# Microcontroller.net
KiCad netlist of a schematic drawn in Altium Designer
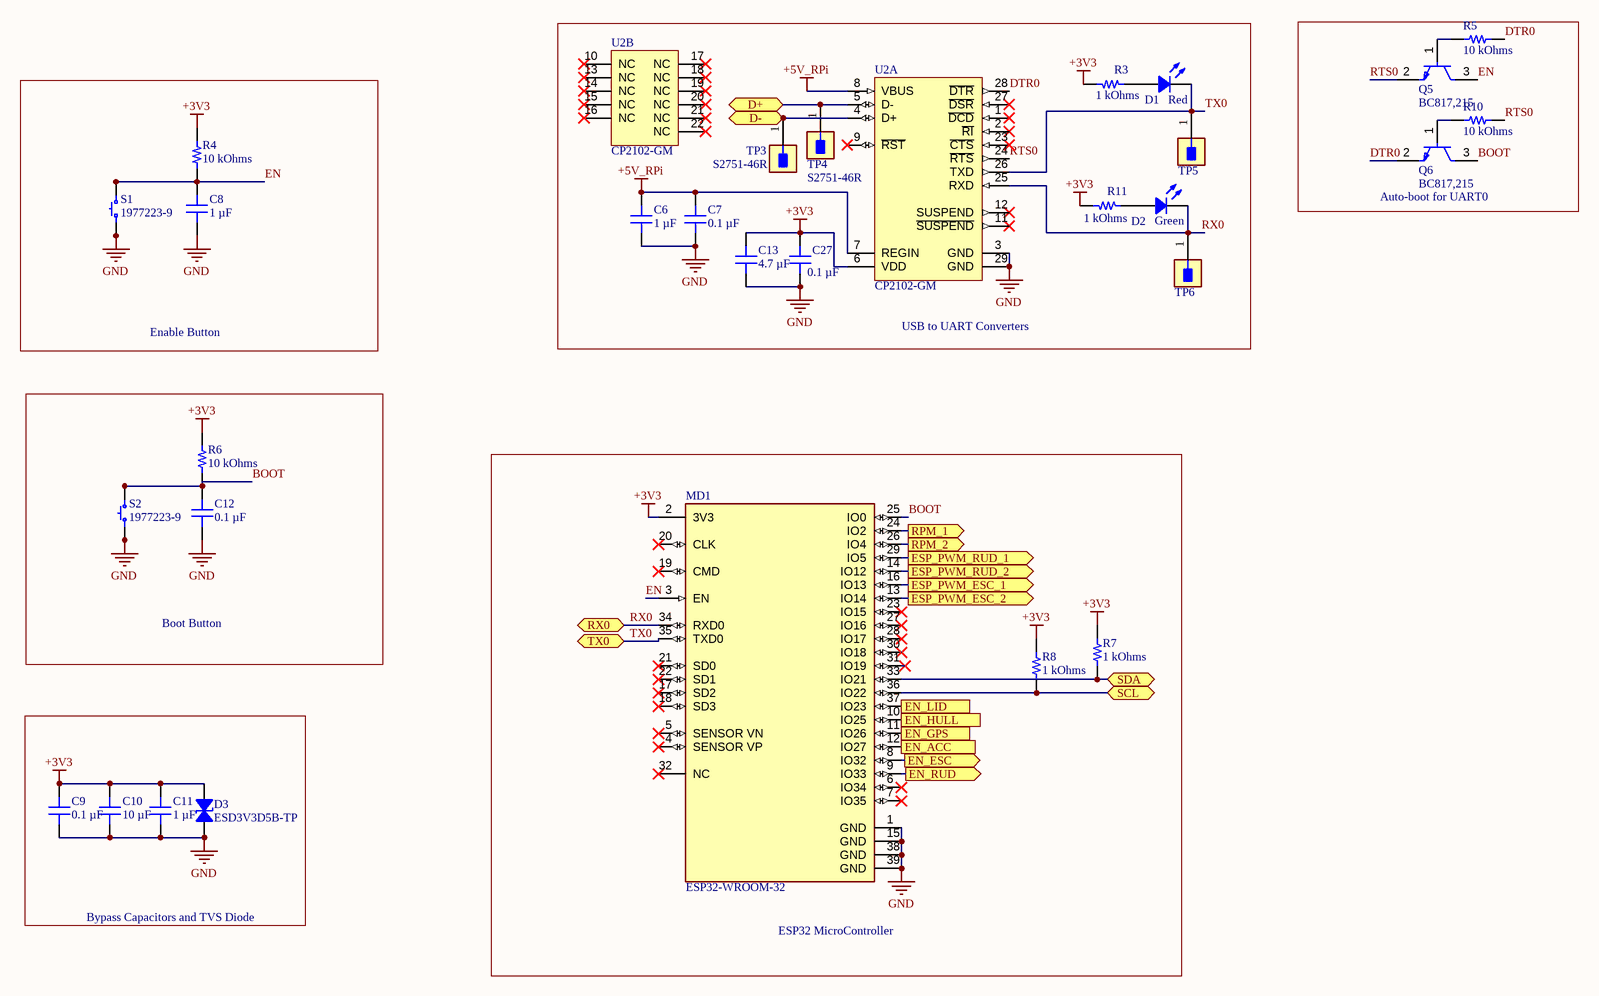
[diagram p0: Microcontroller.SchDoc]

(export (version "E")
  (design (tool "Eeschema 10.0.6"))
  (components
    (comp (ref "C6")
      (value "1 µF")
      (footprint "CAP 0603_1608")
      (description "CAP CER 1UF 35V X6S 0603")
      (fields
        (field (name "PART NUMBER") "GRT188C8YA105KE13D")
        (field (name "MANUFACTURER") "Murata Electronics")
      )
      (libsource (lib "Celestial Altium Library - altium_library") (part "Capacitor"))
    )
    (comp (ref "C7")
      (value "0.1 µF")
      (footprint "CAP 0603_1608")
      (description "CAP CER 0.1UF 25V X7R 0603")
      (fields (field (name "PART NUMBER") "C0603X104M3RAC7867") (field (name "MANUFACTURER") "KEMET"))
      (libsource (lib "Celestial Altium Library - altium_library") (part "Capacitor"))
    )
    (comp (ref "C8")
      (value "1 µF")
      (footprint "CAP 0603_1608")
      (description "CAP CER 1UF 16V X7R 0603")
      (fields (field (name "PART NUMBER") "CM105X7R105K16ATH") (field (name "MANUFACTURER") "KYOCERA AVX"))
      (libsource (lib "Celestial Altium Library - altium_library") (part "Capacitor"))
    )
    (comp (ref "C9")
      (value "0.1 µF")
      (footprint "CAP 0603_1608")
      (description "CAP CER 0.1UF 25V X7R 0603")
      (fields (field (name "PART NUMBER") "C0603X104M3RAC7867") (field (name "MANUFACTURER") "KEMET"))
      (libsource (lib "Celestial Altium Library - altium_library") (part "Capacitor"))
    )
    (comp (ref "C10")
      (value "10 µF")
      (footprint "CAP 0603_1608")
      (description "CAP CER 10UF 16V X5R 0603")
      (fields
        (field (name "PART NUMBER") "GRT188R61C106ME13D")
        (field (name "MANUFACTURER") "Murata Electronics")
      )
      (libsource (lib "Celestial Altium Library - altium_library") (part "Capacitor"))
    )
    (comp (ref "C11")
      (value "1 µF")
      (footprint "CAP 0603_1608")
      (description "CAP CER 1UF 16V X7R 0603")
      (fields (field (name "PART NUMBER") "CM105X7R105K16ATH") (field (name "MANUFACTURER") "KYOCERA AVX"))
      (libsource (lib "Celestial Altium Library - altium_library") (part "Capacitor"))
    )
    (comp (ref "C12")
      (value "0.1 µF")
      (footprint "CAP 0603_1608")
      (description "CAP CER 0.1UF 25V X7R 0603")
      (fields (field (name "PART NUMBER") "C0603X104M3RAC7867") (field (name "MANUFACTURER") "KEMET"))
      (libsource (lib "Celestial Altium Library - altium_library") (part "Capacitor"))
    )
    (comp (ref "C13")
      (value "4.7 µF")
      (footprint "CAP 0603_1608")
      (description "CAP CER 4.7UF 25V X6S 0603")
      (fields
        (field (name "PART NUMBER") "GRT188C81E475KE13D")
        (field (name "MANUFACTURER") "Murata Electronics")
      )
      (libsource (lib "Celestial Altium Library - altium_library") (part "Capacitor"))
    )
    (comp (ref "C27")
      (value "0.1 µF")
      (footprint "CAP 0603_1608")
      (description "CAP CER 0.1UF 25V X7R 0603")
      (fields (field (name "PART NUMBER") "C0603X104M3RAC7867") (field (name "MANUFACTURER") "KEMET"))
      (libsource (lib "Celestial Altium Library - altium_library") (part "Capacitor"))
    )
    (comp (ref "D1")
      (value "Red")
      (footprint "LED 0805_2012 RED")
      (description "LED RED CLEAR CHIP SMD")
      (fields (field (name "PART NUMBER") "XZUR54W-1") (field (name "MANUFACTURER") "SunLED"))
      (libsource (lib "Celestial Altium Library - altium_library") (part "LED"))
    )
    (comp (ref "D2")
      (value "Green")
      (footprint "LED 0805_2012 GREEN")
      (description "LED GREEN CLEAR CHIP SMD")
      (fields (field (name "PART NUMBER") "XZVG54W-1") (field (name "MANUFACTURER") "SunLED"))
      (libsource (lib "Celestial Altium Library - altium_library") (part "LED"))
    )
    (comp (ref "D3")
      (value "ESD3V3D5B-TP")
      (footprint "SOD523F")
      (description "TVS DIODE 3.3VWM 12VC SOD523")
      (fields (field (name "MANUFACTURER") "Micro Commercial Co"))
      (libsource (lib "Celestial Altium Library - altium_library") (part "Diode TVS"))
    )
    (comp (ref "MD1")
      (value "ESP32-WROOM-32")
      (footprint "FP-ESP32-WROOM-32-MFG")
      (description "RX TXRX MOD WIFI SURFACE MOUNT")
      (libsource (lib "Altium Content Vault") (part "ee866abf0b6c51247b7f5cdebf2f250"))
    )
    (comp (ref "Q5")
      (value "BC817,215")
      (footprint "FP-SOT23-IPC_C")
      (description "TRANS NPN 45V 500MA TO236AB")
      (libsource (lib "Altium Content Vault") (part "b44e953556f554d0102664c7d152cb4"))
    )
    (comp (ref "Q6")
      (value "BC817,215")
      (footprint "FP-SOT23-IPC_C")
      (description "TRANS NPN 45V 500MA TO236AB")
      (libsource (lib "Altium Content Vault") (part "b44e953556f554d0102664c7d152cb4"))
    )
    (comp (ref "R3")
      (value "1 kOhms")
      (footprint "RES 0603_1608")
      (description "RES SMD 1K OHM 1% 1/10W 0603")
      (fields (field (name "PART NUMBER") "CRCW06031K00FKEB") (field (name "MANUFACTURER") "Vishay Dale"))
      (libsource (lib "Celestial Altium Library - altium_library") (part "Resistor"))
    )
    (comp (ref "R4")
      (value "10 kOhms")
      (footprint "RES 0603_1608")
      (description "RES SMD 10K OHM 1% 1/10W 0603")
      (fields (field (name "PART NUMBER") "RT0603FRE0710KL") (field (name "MANUFACTURER") "Yageo"))
      (libsource (lib "Celestial Altium Library - altium_library") (part "Resistor"))
    )
    (comp (ref "R5")
      (value "10 kOhms")
      (footprint "RES 0603_1608")
      (description "RES 10K OHM 1% 1/5W 0603")
      (fields (field (name "PART NUMBER") "RC0603FR-7W10KL") (field (name "MANUFACTURER") "Yageo"))
      (libsource (lib "Celestial Altium Library - altium_library") (part "Resistor"))
    )
    (comp (ref "R6")
      (value "10 kOhms")
      (footprint "RES 0603_1608")
      (description "RES SMD 10K OHM 1% 1/10W 0603")
      (fields (field (name "PART NUMBER") "RT0603FRE0710KL") (field (name "MANUFACTURER") "Yageo"))
      (libsource (lib "Celestial Altium Library - altium_library") (part "Resistor"))
    )
    (comp (ref "R7")
      (value "1 kOhms")
      (footprint "RES 0603_1608")
      (description "RES SMD 1K OHM 1% 1/10W 0603")
      (fields (field (name "PART NUMBER") "CRCW06031K00FKEB") (field (name "MANUFACTURER") "Vishay Dale"))
      (libsource (lib "Celestial Altium Library - altium_library") (part "Resistor"))
    )
    (comp (ref "R8")
      (value "1 kOhms")
      (footprint "RES 0603_1608")
      (description "RES SMD 1K OHM 1% 1/10W 0603")
      (fields (field (name "PART NUMBER") "CRCW06031K00FKEB") (field (name "MANUFACTURER") "Vishay Dale"))
      (libsource (lib "Celestial Altium Library - altium_library") (part "Resistor"))
    )
    (comp (ref "R10")
      (value "10 kOhms")
      (footprint "RES 0603_1608")
      (description "RES 10K OHM 1% 1/5W 0603")
      (fields (field (name "PART NUMBER") "RC0603FR-7W10KL") (field (name "MANUFACTURER") "Yageo"))
      (libsource (lib "Celestial Altium Library - altium_library") (part "Resistor"))
    )
    (comp (ref "R11")
      (value "1 kOhms")
      (footprint "RES 0603_1608")
      (description "RES SMD 1K OHM 1% 1/10W 0603")
      (fields (field (name "PART NUMBER") "CRCW06031K00FKEB") (field (name "MANUFACTURER") "Vishay Dale"))
      (libsource (lib "Celestial Altium Library - altium_library") (part "Resistor"))
    )
    (comp (ref "S1")
      (value "1977223-9")
      (footprint "TE FSM4JSMA")
      (description "SWITCH TACTILE SPST-NO 0.05A 24V")
      (fields (field (name "MANUFACTURER") "TE Connectivity ALCOSWITCH Switches"))
      (libsource (lib "Celestial Altium Library - altium_library") (part "SPST-NO 4 PIN"))
    )
    (comp (ref "S2")
      (value "1977223-9")
      (footprint "TE FSM4JSMA")
      (description "SWITCH TACTILE SPST-NO 0.05A 24V")
      (fields (field (name "MANUFACTURER") "TE Connectivity ALCOSWITCH Switches"))
      (libsource (lib "Celestial Altium Library - altium_library") (part "SPST-NO 4 PIN"))
    )
    (comp (ref "TP3")
      (value "S2751-46R")
      (footprint "FP-S2751-46R-MFG")
      (description "Conn Test Point 1 POS Solder ST SMD 1 Port T/R")
      (libsource (lib "Americas- Environmental Engineering Club- University of Victoria") (part "dd45045ce8184df9e99e12baf3f412c"))
    )
    (comp (ref "TP4")
      (value "S2751-46R")
      (footprint "FP-S2751-46R-MFG")
      (description "Conn Test Point 1 POS Solder ST SMD 1 Port T/R")
      (libsource (lib "Americas- Environmental Engineering Club- University of Victoria") (part "dd45045ce8184df9e99e12baf3f412c"))
    )
    (comp (ref "TP5")
      (value "S2751-46R")
      (footprint "FP-S2751-46R-MFG")
      (description "Conn Test Point 1 POS Solder ST SMD 1 Port T/R")
      (libsource (lib "Americas- Environmental Engineering Club- University of Victoria") (part "dd45045ce8184df9e99e12baf3f412c"))
    )
    (comp (ref "TP6")
      (value "S2751-46R")
      (footprint "FP-S2751-46R-MFG")
      (description "Conn Test Point 1 POS Solder ST SMD 1 Port T/R")
      (libsource (lib "Americas- Environmental Engineering Club- University of Victoria") (part "dd45045ce8184df9e99e12baf3f412c"))
    )
    (comp (ref "U2")
      (value "CP2102-GM")
      (footprint "SLAB-QFN-28-3125x3125TP_N")
      (description "Single-Chip USB to UART Bridge, 1024 Bytes EEPROM, -40 to 85 degC, 28-pin QFN, Tube")
      (fields (field (name "MANUFACTURER") "Silicon Labs"))
      (libsource (lib "Altium Content Vault") (part "SLAB-CP210X-QFN-28-29"))
    )
  )
  (nets
    (net (code "1") (name "+3V3") (class "Default")
      (node (ref "C10") (pin "2") (pinfunction "2_2") (pintype "passive"))
      (node (ref "C11") (pin "2") (pinfunction "2_2") (pintype "passive"))
      (node (ref "C13") (pin "2") (pinfunction "2_2") (pintype "passive"))
      (node (ref "C27") (pin "2") (pinfunction "2_2") (pintype "passive"))
      (node (ref "C9") (pin "2") (pinfunction "2_2") (pintype "passive"))
      (node (ref "D3") (pin "2") (pinfunction "2_2") (pintype "passive"))
      (node (ref "MD1") (pin "2") (pinfunction "3V3_2") (pintype "power_in"))
      (node (ref "R11") (pin "2") (pinfunction "2_2") (pintype "passive"))
      (node (ref "R3") (pin "2") (pinfunction "2_2") (pintype "passive"))
      (node (ref "R4") (pin "2") (pinfunction "2_2") (pintype "passive"))
      (node (ref "R6") (pin "2") (pinfunction "2_2") (pintype "passive"))
      (node (ref "R7") (pin "2") (pinfunction "2_2") (pintype "passive"))
      (node (ref "R8") (pin "2") (pinfunction "2_2") (pintype "passive"))
      (node (ref "U2") (pin "6") (pinfunction "VDD_6") (pintype "power_in"))
    )
    (net (code "2") (name "+5V_RPi") (class "Default")
      (node (ref "C6") (pin "2") (pinfunction "2_2") (pintype "passive"))
      (node (ref "C7") (pin "2") (pinfunction "2_2") (pintype "passive"))
      (node (ref "U2") (pin "7") (pinfunction "REGIN_7") (pintype "power_in"))
      (node (ref "U2") (pin "8") (pinfunction "VBUS_8") (pintype "input"))
    )
    (net (code "3") (name "/BOOT") (class "Default")
      (node (ref "C12") (pin "2") (pinfunction "2_2") (pintype "passive"))
      (node (ref "MD1") (pin "25") (pinfunction "IO0_25") (pintype "bidirectional"))
      (node (ref "Q6") (pin "3") (pinfunction "C_3") (pintype "passive"))
      (node (ref "R6") (pin "1") (pinfunction "1_1") (pintype "passive"))
      (node (ref "S2") (pin "3") (pinfunction "3_3") (pintype "passive"))
      (node (ref "S2") (pin "4") (pinfunction "4_4") (pintype "passive"))
    )
    (net (code "4") (name "/D+") (class "Default")
      (node (ref "TP4") (pin "1") (pinfunction "1_1") (pintype "passive"))
      (node (ref "U2") (pin "5") (pinfunction "D-_5") (pintype "bidirectional"))
    )
    (net (code "5") (name "/D-") (class "Default")
      (node (ref "TP3") (pin "1") (pinfunction "1_1") (pintype "passive"))
      (node (ref "U2") (pin "4") (pinfunction "D+_4") (pintype "bidirectional"))
    )
    (net (code "6") (name "/DTR0") (class "Default")
      (node (ref "Q6") (pin "2") (pinfunction "E_2") (pintype "passive"))
      (node (ref "R5") (pin "2") (pinfunction "2_2") (pintype "passive"))
      (node (ref "U2") (pin "28") (pinfunction "~{DTR}_28") (pintype "output"))
    )
    (net (code "7") (name "/EN") (class "Default")
      (node (ref "C8") (pin "2") (pinfunction "2_2") (pintype "passive"))
      (node (ref "MD1") (pin "3") (pinfunction "EN_3") (pintype "input"))
      (node (ref "Q5") (pin "3") (pinfunction "C_3") (pintype "passive"))
      (node (ref "R4") (pin "1") (pinfunction "1_1") (pintype "passive"))
      (node (ref "S1") (pin "3") (pinfunction "3_3") (pintype "passive"))
      (node (ref "S1") (pin "4") (pinfunction "4_4") (pintype "passive"))
    )
    (net (code "8") (name "/EN_ACC") (class "Default")
      (node (ref "MD1") (pin "12") (pinfunction "IO27_12") (pintype "bidirectional"))
    )
    (net (code "9") (name "/EN_ESC") (class "Default")
      (node (ref "MD1") (pin "8") (pinfunction "IO32_8") (pintype "bidirectional"))
    )
    (net (code "10") (name "/EN_GPS") (class "Default")
      (node (ref "MD1") (pin "11") (pinfunction "IO26_11") (pintype "bidirectional"))
    )
    (net (code "11") (name "/EN_HULL") (class "Default")
      (node (ref "MD1") (pin "10") (pinfunction "IO25_10") (pintype "bidirectional"))
    )
    (net (code "12") (name "/EN_LID") (class "Default")
      (node (ref "MD1") (pin "37") (pinfunction "IO23_37") (pintype "bidirectional"))
    )
    (net (code "13") (name "/EN_RUD") (class "Default")
      (node (ref "MD1") (pin "9") (pinfunction "IO33_9") (pintype "bidirectional"))
    )
    (net (code "14") (name "/ESP_PWM_ESC_1") (class "Default")
      (node (ref "MD1") (pin "16") (pinfunction "IO13_16") (pintype "bidirectional"))
    )
    (net (code "15") (name "/ESP_PWM_ESC_2") (class "Default")
      (node (ref "MD1") (pin "13") (pinfunction "IO14_13") (pintype "bidirectional"))
    )
    (net (code "16") (name "/ESP_PWM_RUD_1") (class "Default")
      (node (ref "MD1") (pin "29") (pinfunction "IO5_29") (pintype "bidirectional"))
    )
    (net (code "17") (name "/ESP_PWM_RUD_2") (class "Default")
      (node (ref "MD1") (pin "14") (pinfunction "IO12_14") (pintype "bidirectional"))
    )
    (net (code "18") (name "/RPM_1") (class "Default")
      (node (ref "MD1") (pin "24") (pinfunction "IO2_24") (pintype "bidirectional"))
    )
    (net (code "19") (name "/RPM_2") (class "Default")
      (node (ref "MD1") (pin "26") (pinfunction "IO4_26") (pintype "bidirectional"))
    )
    (net (code "20") (name "/RTS0") (class "Default")
      (node (ref "Q5") (pin "2") (pinfunction "E_2") (pintype "passive"))
      (node (ref "R10") (pin "2") (pinfunction "2_2") (pintype "passive"))
      (node (ref "U2") (pin "24") (pinfunction "~{RTS}_24") (pintype "output"))
    )
    (net (code "21") (name "/RX0") (class "Default")
      (node (ref "D2") (pin "2") (pinfunction "2_2") (pintype "passive"))
      (node (ref "MD1") (pin "34") (pinfunction "RXD0_34") (pintype "bidirectional"))
      (node (ref "TP6") (pin "1") (pinfunction "1_1") (pintype "passive"))
      (node (ref "U2") (pin "25") (pinfunction "RXD_25") (pintype "input"))
    )
    (net (code "22") (name "/SCL") (class "Default")
      (node (ref "MD1") (pin "36") (pinfunction "IO22_36") (pintype "bidirectional"))
      (node (ref "R8") (pin "1") (pinfunction "1_1") (pintype "passive"))
    )
    (net (code "23") (name "/SDA") (class "Default")
      (node (ref "MD1") (pin "33") (pinfunction "IO21_33") (pintype "bidirectional"))
      (node (ref "R7") (pin "1") (pinfunction "1_1") (pintype "passive"))
    )
    (net (code "24") (name "/TX0") (class "Default")
      (node (ref "D1") (pin "2") (pinfunction "2_2") (pintype "passive"))
      (node (ref "MD1") (pin "35") (pinfunction "TXD0_35") (pintype "bidirectional"))
      (node (ref "TP5") (pin "1") (pinfunction "1_1") (pintype "passive"))
      (node (ref "U2") (pin "26") (pinfunction "TXD_26") (pintype "output"))
    )
    (net (code "25") (name "GND") (class "Default")
      (node (ref "C10") (pin "1") (pinfunction "1_1") (pintype "passive"))
      (node (ref "C11") (pin "1") (pinfunction "1_1") (pintype "passive"))
      (node (ref "C12") (pin "1") (pinfunction "1_1") (pintype "passive"))
      (node (ref "C13") (pin "1") (pinfunction "1_1") (pintype "passive"))
      (node (ref "C27") (pin "1") (pinfunction "1_1") (pintype "passive"))
      (node (ref "C6") (pin "1") (pinfunction "1_1") (pintype "passive"))
      (node (ref "C7") (pin "1") (pinfunction "1_1") (pintype "passive"))
      (node (ref "C8") (pin "1") (pinfunction "1_1") (pintype "passive"))
      (node (ref "C9") (pin "1") (pinfunction "1_1") (pintype "passive"))
      (node (ref "D3") (pin "1") (pinfunction "1_1") (pintype "passive"))
      (node (ref "MD1") (pin "1") (pinfunction "GND_1") (pintype "power_in"))
      (node (ref "MD1") (pin "15") (pinfunction "GND_15") (pintype "power_in"))
      (node (ref "MD1") (pin "38") (pinfunction "GND_38") (pintype "power_in"))
      (node (ref "MD1") (pin "39") (pinfunction "GND_39") (pintype "power_in"))
      (node (ref "S1") (pin "1") (pinfunction "1_1") (pintype "passive"))
      (node (ref "S1") (pin "2") (pinfunction "2_2") (pintype "passive"))
      (node (ref "S2") (pin "1") (pinfunction "1_1") (pintype "passive"))
      (node (ref "S2") (pin "2") (pinfunction "2_2") (pintype "passive"))
      (node (ref "U2") (pin "29") (pinfunction "GND_29") (pintype "power_in"))
      (node (ref "U2") (pin "3") (pinfunction "GND_3") (pintype "power_in"))
    )
    (net (code "26") (name "Net-(D1-Pad1)") (class "Default")
      (node (ref "D1") (pin "1") (pinfunction "1_1") (pintype "passive"))
      (node (ref "R3") (pin "1") (pinfunction "1_1") (pintype "passive"))
    )
    (net (code "27") (name "Net-(D2-Pad1)") (class "Default")
      (node (ref "D2") (pin "1") (pinfunction "1_1") (pintype "passive"))
      (node (ref "R11") (pin "1") (pinfunction "1_1") (pintype "passive"))
    )
    (net (code "28") (name "Net-(Q5-B)") (class "Default")
      (node (ref "Q5") (pin "1") (pinfunction "B_1") (pintype "passive"))
      (node (ref "R5") (pin "1") (pinfunction "1_1") (pintype "passive"))
    )
    (net (code "29") (name "Net-(Q6-B)") (class "Default")
      (node (ref "Q6") (pin "1") (pinfunction "B_1") (pintype "passive"))
      (node (ref "R10") (pin "1") (pinfunction "1_1") (pintype "passive"))
    )
    (net (code "30") (name "unconnected-(MD1-CLK-Pad20)") (class "Default")
      (node (ref "MD1") (pin "20") (pinfunction "CLK_20") (pintype "bidirectional+no_connect"))
    )
    (net (code "31") (name "unconnected-(MD1-CMD-Pad19)") (class "Default")
      (node (ref "MD1") (pin "19") (pinfunction "CMD_19") (pintype "bidirectional+no_connect"))
    )
    (net (code "32") (name "unconnected-(MD1-IO15-Pad23)") (class "Default")
      (node (ref "MD1") (pin "23") (pinfunction "IO15_23") (pintype "bidirectional+no_connect"))
    )
    (net (code "33") (name "unconnected-(MD1-IO16-Pad27)") (class "Default")
      (node (ref "MD1") (pin "27") (pinfunction "IO16_27") (pintype "bidirectional+no_connect"))
    )
    (net (code "34") (name "unconnected-(MD1-IO17-Pad28)") (class "Default")
      (node (ref "MD1") (pin "28") (pinfunction "IO17_28") (pintype "bidirectional+no_connect"))
    )
    (net (code "35") (name "unconnected-(MD1-IO18-Pad30)") (class "Default")
      (node (ref "MD1") (pin "30") (pinfunction "IO18_30") (pintype "bidirectional+no_connect"))
    )
    (net (code "36") (name "unconnected-(MD1-IO19-Pad31)") (class "Default")
      (node (ref "MD1") (pin "31") (pinfunction "IO19_31") (pintype "bidirectional+no_connect"))
    )
    (net (code "37") (name "unconnected-(MD1-IO34-Pad6)") (class "Default")
      (node (ref "MD1") (pin "6") (pinfunction "IO34_6") (pintype "bidirectional+no_connect"))
    )
    (net (code "38") (name "unconnected-(MD1-IO35-Pad7)") (class "Default")
      (node (ref "MD1") (pin "7") (pinfunction "IO35_7") (pintype "bidirectional+no_connect"))
    )
    (net (code "39") (name "unconnected-(MD1-NC-Pad32)") (class "Default")
      (node (ref "MD1") (pin "32") (pinfunction "NC_32") (pintype "passive+no_connect"))
    )
    (net (code "40") (name "unconnected-(MD1-SD0-Pad21)") (class "Default")
      (node (ref "MD1") (pin "21") (pinfunction "SD0_21") (pintype "bidirectional+no_connect"))
    )
    (net (code "41") (name "unconnected-(MD1-SD1-Pad22)") (class "Default")
      (node (ref "MD1") (pin "22") (pinfunction "SD1_22") (pintype "bidirectional+no_connect"))
    )
    (net (code "42") (name "unconnected-(MD1-SD2-Pad17)") (class "Default")
      (node (ref "MD1") (pin "17") (pinfunction "SD2_17") (pintype "bidirectional+no_connect"))
    )
    (net (code "43") (name "unconnected-(MD1-SD3-Pad18)") (class "Default")
      (node (ref "MD1") (pin "18") (pinfunction "SD3_18") (pintype "bidirectional+no_connect"))
    )
    (net (code "44") (name "unconnected-(MD1-SENSOR_VN-Pad5)") (class "Default")
      (node (ref "MD1") (pin "5") (pinfunction "SENSOR_VN_5") (pintype "bidirectional+no_connect"))
    )
    (net (code "45") (name "unconnected-(MD1-SENSOR_VP-Pad4)") (class "Default")
      (node (ref "MD1") (pin "4") (pinfunction "SENSOR_VP_4") (pintype "bidirectional+no_connect"))
    )
    (net (code "46") (name "unconnected-(U2A-SUSPEND-Pad12)") (class "Default")
      (node (ref "U2") (pin "12") (pinfunction "SUSPEND_12") (pintype "output+no_connect"))
    )
    (net (code "47") (name "unconnected-(U2A-~{CTS}-Pad23)") (class "Default")
      (node (ref "U2") (pin "23") (pinfunction "~{CTS}_23") (pintype "input+no_connect"))
    )
    (net (code "48") (name "unconnected-(U2A-~{DCD}-Pad1)") (class "Default")
      (node (ref "U2") (pin "1") (pinfunction "~{DCD}_1") (pintype "input+no_connect"))
    )
    (net (code "49") (name "unconnected-(U2A-~{DSR}-Pad27)") (class "Default")
      (node (ref "U2") (pin "27") (pinfunction "~{DSR}_27") (pintype "input+no_connect"))
    )
    (net (code "50") (name "unconnected-(U2A-~{RI}-Pad2)") (class "Default")
      (node (ref "U2") (pin "2") (pinfunction "~{RI}_2") (pintype "input+no_connect"))
    )
    (net (code "51") (name "unconnected-(U2A-~{RST}-Pad9)") (class "Default")
      (node (ref "U2") (pin "9") (pinfunction "~{RST}_9") (pintype "bidirectional+no_connect"))
    )
    (net (code "52") (name "unconnected-(U2A-~{SUSPEND}-Pad11)") (class "Default")
      (node (ref "U2") (pin "11") (pinfunction "~{SUSPEND}_11") (pintype "output+no_connect"))
    )
    (net (code "53") (name "unconnected-(U2B-NC-Pad10)") (class "Default")
      (node (ref "U2") (pin "10") (pinfunction "NC_10") (pintype "passive+no_connect"))
    )
    (net (code "54") (name "unconnected-(U2B-NC-Pad13)") (class "Default")
      (node (ref "U2") (pin "13") (pinfunction "NC_13") (pintype "passive+no_connect"))
    )
    (net (code "55") (name "unconnected-(U2B-NC-Pad14)") (class "Default")
      (node (ref "U2") (pin "14") (pinfunction "NC_14") (pintype "passive+no_connect"))
    )
    (net (code "56") (name "unconnected-(U2B-NC-Pad15)") (class "Default")
      (node (ref "U2") (pin "15") (pinfunction "NC_15") (pintype "passive+no_connect"))
    )
    (net (code "57") (name "unconnected-(U2B-NC-Pad16)") (class "Default")
      (node (ref "U2") (pin "16") (pinfunction "NC_16") (pintype "passive+no_connect"))
    )
    (net (code "58") (name "unconnected-(U2B-NC-Pad17)") (class "Default")
      (node (ref "U2") (pin "17") (pinfunction "NC_17") (pintype "passive+no_connect"))
    )
    (net (code "59") (name "unconnected-(U2B-NC-Pad18)") (class "Default")
      (node (ref "U2") (pin "18") (pinfunction "NC_18") (pintype "passive+no_connect"))
    )
    (net (code "60") (name "unconnected-(U2B-NC-Pad19)") (class "Default")
      (node (ref "U2") (pin "19") (pinfunction "NC_19") (pintype "passive+no_connect"))
    )
    (net (code "61") (name "unconnected-(U2B-NC-Pad20)") (class "Default")
      (node (ref "U2") (pin "20") (pinfunction "NC_20") (pintype "passive+no_connect"))
    )
    (net (code "62") (name "unconnected-(U2B-NC-Pad21)") (class "Default")
      (node (ref "U2") (pin "21") (pinfunction "NC_21") (pintype "passive+no_connect"))
    )
    (net (code "63") (name "unconnected-(U2B-NC-Pad22)") (class "Default")
      (node (ref "U2") (pin "22") (pinfunction "NC_22") (pintype "passive+no_connect"))
    )
  )
)
